# SDMMC_RV1126B.net
KiCad netlist of a schematic drawn in Altium Designer
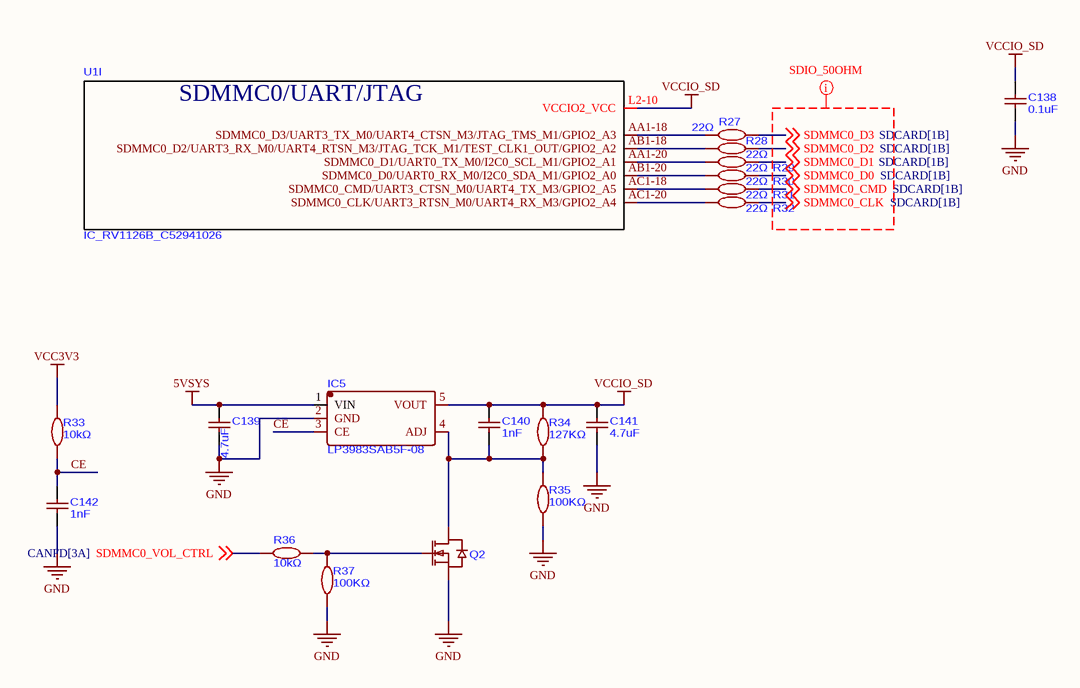
[diagram p0: SDMMC RV1126B.SchDoc]

(export (version "E")
  (design (tool "Eeschema 10.0.6"))
  (components
    (comp (ref "C138")
      (value "0.1uF")
      (footprint "C0201")
      (description "0.1uF ±10% 6.3V Ceramic Capacitor X5R 0201")
      (libsource (lib "Schlib1") (part "CAP_100nF-6.3V-10%-0201_1"))
    )
    (comp (ref "C139")
      (value "4.7uF")
      (footprint "C0402")
      (description "4.7uF ±10% 16V Ceramic Capacitor X5R 0402")
      (libsource (lib "Schlib1") (part "CAP_4.7uF-16V-10%-0402"))
    )
    (comp (ref "C140")
      (value "1nF")
      (footprint "C0201")
      (description "CAP CER 1nF 50V X7R 0201")
      (libsource (lib "Schlib1") (part "CAP_1nF-50V-10%-0201"))
    )
    (comp (ref "C141")
      (value "4.7uF")
      (footprint "C0402")
      (description "4.7uF ±10% 16V Ceramic Capacitor X5R 0402")
      (libsource (lib "Schlib1") (part "CAP_4.7uF-16V-10%-0402"))
    )
    (comp (ref "C142")
      (value "1nF")
      (footprint "C0201")
      (description "CAP CER 1nF 50V X7R 0201")
      (libsource (lib "Schlib1") (part "CAP_1nF-50V-10%-0201"))
    )
    (comp (ref "IC5")
      (value "LP3983SAB5F-08")
      (footprint "SOT-23-5_L3.0-W1.7-P0.95-LS2.8-BR")
      (description "300mA, Ultra-low noise, Small Package Ultra-Fast CMOS LDO Regulator")
      (libsource (lib "Schlib1") (part "LP3983SAB5F-08"))
    )
    (comp (ref "Q2")
      (value "N-CHANEL")
      (footprint "SOT-23-3_L2.9-W1.3-P1.90-LS2.4-BR")
      (description "MOSFET N-CH 20V 3A SOT-23")
      (libsource (lib "Schlib1") (part "JSM2302A-A2SHB"))
    )
    (comp (ref "R27")
      (value "22Ω")
      (footprint "R0201")
      (description "RES 22Ω ±1% 50mW 0201")
      (libsource (lib "Schlib1") (part "RES_22-50mW-1%-0201"))
    )
    (comp (ref "R28")
      (value "22Ω")
      (footprint "R0201")
      (description "RES 22Ω ±1% 50mW 0201")
      (libsource (lib "Schlib1") (part "RES_22-50mW-1%-0201"))
    )
    (comp (ref "R29")
      (value "22Ω")
      (footprint "R0201")
      (description "RES 22Ω ±1% 50mW 0201")
      (libsource (lib "Schlib1") (part "RES_22-50mW-1%-0201"))
    )
    (comp (ref "R30")
      (value "22Ω")
      (footprint "R0201")
      (description "RES 22Ω ±1% 50mW 0201")
      (libsource (lib "Schlib1") (part "RES_22-50mW-1%-0201"))
    )
    (comp (ref "R31")
      (value "22Ω")
      (footprint "R0201")
      (description "RES 22Ω ±1% 50mW 0201")
      (libsource (lib "Schlib1") (part "RES_22-50mW-1%-0201"))
    )
    (comp (ref "R32")
      (value "22Ω")
      (footprint "R0201")
      (description "RES 22Ω ±1% 50mW 0201")
      (libsource (lib "Schlib1") (part "RES_22-50mW-1%-0201"))
    )
    (comp (ref "R33")
      (value "10kΩ")
      (footprint "R0201")
      (description "RES 10KΩ ±1% 50mW 0201")
      (libsource (lib "Schlib1") (part "RES_10K-50mW-1%-0201"))
    )
    (comp (ref "R34")
      (value "127KΩ")
      (footprint "R0201")
      (description "RES 127kΩ ±1% 50mW 0201")
      (libsource (lib "Schlib1") (part "RES_127K-50mW-1%-0201"))
    )
    (comp (ref "R35")
      (value "100KΩ")
      (footprint "R0201")
      (description "RES 100kΩ ±1% 50mW 0201")
      (libsource (lib "Schlib1") (part "RES_100K-50mW-1%-0201"))
    )
    (comp (ref "R36")
      (value "10kΩ")
      (footprint "R0201")
      (description "RES 10KΩ ±1% 50mW 0201")
      (libsource (lib "Schlib1") (part "RES_10K-50mW-1%-0201"))
    )
    (comp (ref "R37")
      (value "100KΩ")
      (footprint "R0201")
      (description "47kΩ 50mW 25V Thick Film Resistor ±1% ±200ppm/℃ 0201 Chip Resistor - Surface Mount RoHS")
      (libsource (lib "Schlib1") (part "RES_47K-50mW-1%-0201"))
    )
    (comp (ref "U1")
      (value "IC_RV1126B_C52941026")
      (footprint "CCSP-491_L14.0-W14.0-TL_RV1126B")
      (libsource (lib "Schlib1") (part "IC_RV1126B_C52941026"))
    )
  )
  (nets
    (net (code "2") (name "/CE") (class "Default")
      (node (ref "C142") (pin "2") (pinfunction "2_2") (pintype "passive"))
      (node (ref "IC5") (pin "3") (pinfunction "CE_3") (pintype "passive"))
      (node (ref "R33") (pin "2") (pinfunction "2_2") (pintype "passive"))
    )
    (net (code "3") (name "5VSYS") (class "Default")
      (node (ref "C139") (pin "2") (pinfunction "2_2") (pintype "passive"))
      (node (ref "IC5") (pin "1") (pinfunction "VIN_1") (pintype "passive"))
    )
    (net (code "4") (name "GND") (class "Default")
      (node (ref "C138") (pin "2") (pinfunction "2_2") (pintype "passive"))
      (node (ref "C139") (pin "1") (pinfunction "1_1") (pintype "passive"))
      (node (ref "C141") (pin "2") (pinfunction "2_2") (pintype "passive"))
      (node (ref "C142") (pin "1") (pinfunction "1_1") (pintype "passive"))
      (node (ref "IC5") (pin "2") (pinfunction "GND_2") (pintype "passive"))
      (node (ref "Q2") (pin "2") (pinfunction "S_2") (pintype "passive"))
      (node (ref "R35") (pin "1") (pinfunction "1_1") (pintype "passive"))
      (node (ref "R37") (pin "1") (pinfunction "1_1") (pintype "passive"))
    )
    (net (code "5") (name "Net-(IC5-ADJ)") (class "Default")
      (node (ref "C140") (pin "1") (pinfunction "1_1") (pintype "passive"))
      (node (ref "IC5") (pin "4") (pinfunction "ADJ_4") (pintype "passive"))
      (node (ref "Q2") (pin "3") (pinfunction "D_3") (pintype "passive"))
      (node (ref "R34") (pin "1") (pinfunction "1_1") (pintype "passive"))
      (node (ref "R35") (pin "2") (pinfunction "2_2") (pintype "passive"))
    )
    (net (code "6") (name "Net-(Q2-G)") (class "Default")
      (node (ref "Q2") (pin "1") (pinfunction "G_1") (pintype "passive"))
      (node (ref "R36") (pin "2") (pinfunction "2_2") (pintype "passive"))
      (node (ref "R37") (pin "2") (pinfunction "2_2") (pintype "passive"))
    )
    (net (code "7") (name "Net-(U1I-SDMMC0_CLK{slash}UART3_RTSN_M0{slash}UART4_RX_M3{slash}GPIO2_A4)") (class "Default")
      (node (ref "R32") (pin "1") (pinfunction "1_1") (pintype "passive"))
      (node (ref "U1") (pin "AC1-20") (pinfunction "SDMMC0_CLK/UART3_RTSN_M0/UART4_RX_M3/GPIO2_A4_AC1-20") (pintype "passive"))
    )
    (net (code "8") (name "Net-(U1I-SDMMC0_CMD{slash}UART3_CTSN_M0{slash}UART4_TX_M3{slash}GPIO2_A5)") (class "Default")
      (node (ref "R31") (pin "1") (pinfunction "1_1") (pintype "passive"))
      (node (ref "U1") (pin "AC1-18") (pinfunction "SDMMC0_CMD/UART3_CTSN_M0/UART4_TX_M3/GPIO2_A5_AC1-18") (pintype "passive"))
    )
    (net (code "9") (name "Net-(U1I-SDMMC0_D0{slash}UART0_RX_M0{slash}I2C0_SDA_M1{slash}GPIO2_A0)") (class "Default")
      (node (ref "R30") (pin "1") (pinfunction "1_1") (pintype "passive"))
      (node (ref "U1") (pin "AB1-20") (pinfunction "SDMMC0_D0/UART0_RX_M0/I2C0_SDA_M1/GPIO2_A0_AB1-20") (pintype "passive"))
    )
    (net (code "10") (name "Net-(U1I-SDMMC0_D1{slash}UART0_TX_M0{slash}I2C0_SCL_M1{slash}GPIO2_A1)") (class "Default")
      (node (ref "R29") (pin "1") (pinfunction "1_1") (pintype "passive"))
      (node (ref "U1") (pin "AA1-20") (pinfunction "SDMMC0_D1/UART0_TX_M0/I2C0_SCL_M1/GPIO2_A1_AA1-20") (pintype "passive"))
    )
    (net (code "11") (name "Net-(U1I-SDMMC0_D2{slash}UART3_RX_M0{slash}UART4_RTSN_M3{slash}JTAG_TCK_M1{slash}TEST_CLK1_OUT{slash}GPIO2_A2)") (class "Default")
      (node (ref "R28") (pin "1") (pinfunction "1_1") (pintype "passive"))
      (node (ref "U1") (pin "AB1-18") (pinfunction "SDMMC0_D2/UART3_RX_M0/UART4_RTSN_M3/JTAG_TCK_M1/TEST_CLK1_OUT/GPIO2_A2_AB1-18") (pintype "passive"))
    )
    (net (code "12") (name "Net-(U1I-SDMMC0_D3{slash}UART3_TX_M0{slash}UART4_CTSN_M3{slash}JTAG_TMS_M1{slash}GPIO2_A3)") (class "Default")
      (node (ref "R27") (pin "1") (pinfunction "1_1") (pintype "passive"))
      (node (ref "U1") (pin "AA1-18") (pinfunction "SDMMC0_D3/UART3_TX_M0/UART4_CTSN_M3/JTAG_TMS_M1/GPIO2_A3_AA1-18") (pintype "passive"))
    )
    (net (code "13") (name "SDMMC0_CLK") (class "Default")
      (node (ref "R32") (pin "2") (pinfunction "2_2") (pintype "passive"))
    )
    (net (code "14") (name "SDMMC0_CMD") (class "Default")
      (node (ref "R31") (pin "2") (pinfunction "2_2") (pintype "passive"))
    )
    (net (code "15") (name "SDMMC0_D0") (class "Default")
      (node (ref "R30") (pin "2") (pinfunction "2_2") (pintype "passive"))
    )
    (net (code "16") (name "SDMMC0_D1") (class "Default")
      (node (ref "R29") (pin "2") (pinfunction "2_2") (pintype "passive"))
    )
    (net (code "17") (name "SDMMC0_D2") (class "Default")
      (node (ref "R28") (pin "2") (pinfunction "2_2") (pintype "passive"))
    )
    (net (code "18") (name "SDMMC0_D3") (class "Default")
      (node (ref "R27") (pin "2") (pinfunction "2_2") (pintype "passive"))
    )
    (net (code "19") (name "SDMMC0_VOL_CTRL") (class "Default")
      (node (ref "R36") (pin "1") (pinfunction "1_1") (pintype "passive"))
    )
    (net (code "20") (name "VCC3V3") (class "Default")
      (node (ref "R33") (pin "1") (pinfunction "1_1") (pintype "passive"))
    )
    (net (code "21") (name "VCCIO_SD") (class "Default")
      (node (ref "C138") (pin "1") (pinfunction "1_1") (pintype "passive"))
      (node (ref "C140") (pin "2") (pinfunction "2_2") (pintype "passive"))
      (node (ref "C141") (pin "1") (pinfunction "1_1") (pintype "passive"))
      (node (ref "IC5") (pin "5") (pinfunction "VOUT_5") (pintype "passive"))
      (node (ref "R34") (pin "2") (pinfunction "2_2") (pintype "passive"))
      (node (ref "U1") (pin "L2-10") (pinfunction "VCCIO2_VCC_L2-10") (pintype "passive"))
    )
  )
)
